# LDS3985.net
KiCad netlist of a schematic drawn in Altium Designer
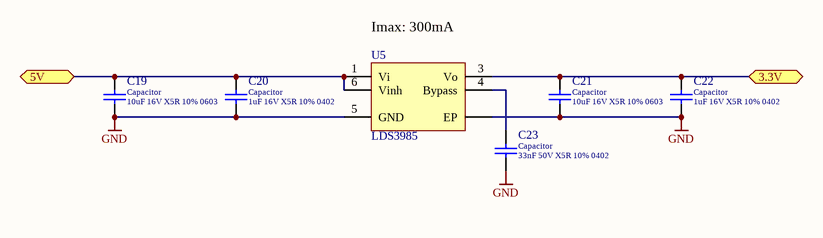
[diagram p0: LDS3985.SchDoc]

(export (version "E")
  (design (tool "Eeschema 10.0.6"))
  (components
    (comp (ref "C19")
      (value "Capacitor")
      (footprint "CAP_SMD:0603")
      (description "Ceramic capacitor")
      (fields
        (field (name "VOLTAGE") "16V")
        (field (name "TOLERANCE") "10%")
        (field (name "ALTIUM_VALUE") "10uF 16V X5R 10% ")
      )
      (libsource (lib "Passive") (part "Capacitor ceramic"))
    )
    (comp (ref "C20")
      (value "Capacitor")
      (footprint "CAP_SMD:0402")
      (description "Ceramic capacitor")
      (fields
        (field (name "VOLTAGE") "16V")
        (field (name "TOLERANCE") "10%")
        (field (name "ALTIUM_VALUE") "1uF 16V X5R 10% ")
      )
      (libsource (lib "Passive") (part "Capacitor ceramic"))
    )
    (comp (ref "C21")
      (value "Capacitor")
      (footprint "CAP_SMD:0603")
      (description "Ceramic capacitor")
      (fields
        (field (name "VOLTAGE") "16V")
        (field (name "TOLERANCE") "10%")
        (field (name "ALTIUM_VALUE") "10uF 16V X5R 10% ")
      )
      (libsource (lib "Passive") (part "Capacitor ceramic"))
    )
    (comp (ref "C22")
      (value "Capacitor")
      (footprint "CAP_SMD:0402")
      (description "Ceramic capacitor")
      (fields
        (field (name "VOLTAGE") "16V")
        (field (name "TOLERANCE") "10%")
        (field (name "ALTIUM_VALUE") "1uF 16V X5R 10% ")
      )
      (libsource (lib "Passive") (part "Capacitor ceramic"))
    )
    (comp (ref "C23")
      (value "Capacitor")
      (footprint "CAP_SMD:0402")
      (description "Ceramic capacitor")
      (fields
        (field (name "VOLTAGE") "50V")
        (field (name "TOLERANCE") "10%")
        (field (name "ALTIUM_VALUE") "33nF 50V X5R 10% ")
      )
      (libsource (lib "Passive") (part "Capacitor ceramic"))
    )
    (comp (ref "U5")
      (value "LDS3985")
      (footprint "QFN_DFN:DFN-6-0.95-3x3")
      (description "300mA CMOS LDO Regulator in ultra small package")
      (libsource (lib "IC_Linear") (part "LDS3985"))
    )
  )
  (nets
    (net (code "1") (name "/3.3V") (class "Default")
      (node (ref "C21") (pin "2") (pinfunction "2_2") (pintype "passive"))
      (node (ref "C22") (pin "2") (pinfunction "2_2") (pintype "passive"))
      (node (ref "U5") (pin "3") (pinfunction "Vo_3") (pintype "passive"))
    )
    (net (code "2") (name "/5V") (class "Default")
      (node (ref "C19") (pin "2") (pinfunction "2_2") (pintype "passive"))
      (node (ref "C20") (pin "2") (pinfunction "2_2") (pintype "passive"))
      (node (ref "U5") (pin "1") (pinfunction "Vi_1") (pintype "passive"))
      (node (ref "U5") (pin "6") (pinfunction "Vinh_6") (pintype "passive"))
    )
    (net (code "3") (name "GND") (class "Default")
      (node (ref "C19") (pin "1") (pinfunction "1_1") (pintype "passive"))
      (node (ref "C20") (pin "1") (pinfunction "1_1") (pintype "passive"))
      (node (ref "C21") (pin "1") (pinfunction "1_1") (pintype "passive"))
      (node (ref "C22") (pin "1") (pinfunction "1_1") (pintype "passive"))
      (node (ref "C23") (pin "1") (pinfunction "1_1") (pintype "passive"))
      (node (ref "U5") (pin "0") (pinfunction "EP_0") (pintype "passive"))
      (node (ref "U5") (pin "5") (pinfunction "GND_5") (pintype "passive"))
    )
    (net (code "4") (name "Net-(U5-Bypass)") (class "Default")
      (node (ref "C23") (pin "2") (pinfunction "2_2") (pintype "passive"))
      (node (ref "U5") (pin "4") (pinfunction "Bypass_4") (pintype "passive"))
    )
  )
)
